# accessories.net
KiCad netlist of a schematic drawn in Altium Designer
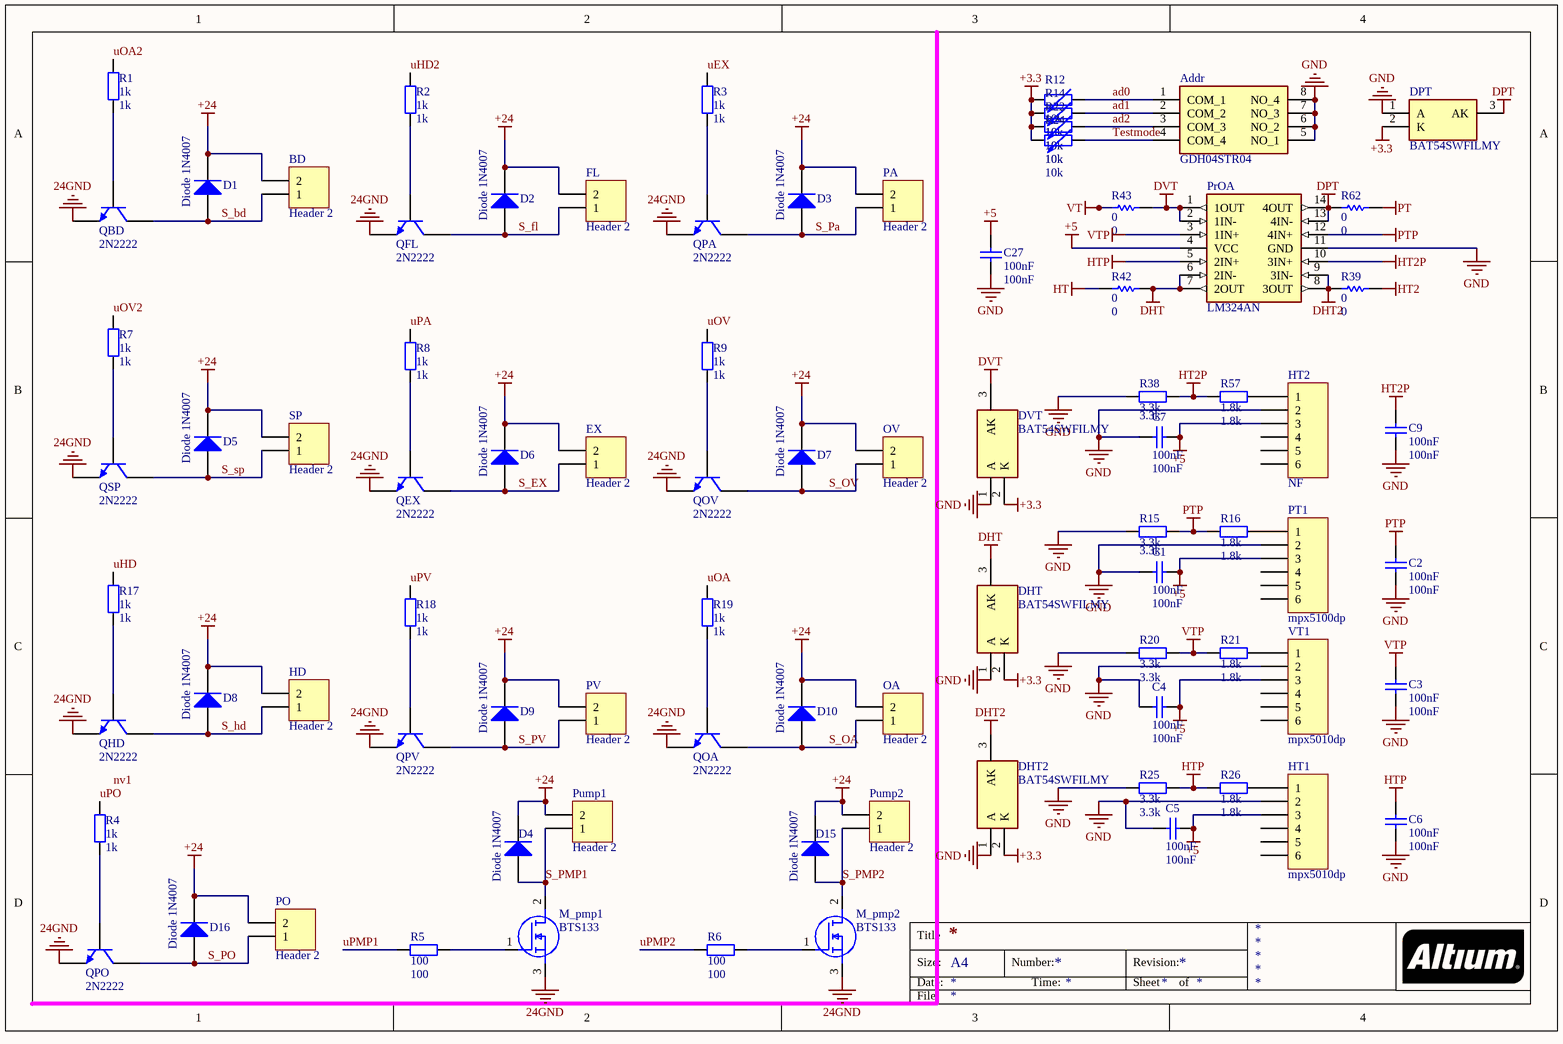
[diagram p0: accessories.SchDoc]

(export (version "E")
  (design (tool "Eeschema 10.0.6"))
  (components
    (comp (ref "Addr")
      (value "GDH04STR04")
      (footprint "SamacSys:GDH04STR04")
      (description "Switch")
      (fields (field (name "MOUSER PART NUMBER") "506-GDH04STR04"))
      (libsource (lib "*") (part "GDH04STR04"))
    )
    (comp (ref "BD")
      (value "Header 2")
      (footprint "PHOENIX2-Right")
      (description "Header, 2-Pin")
      (fields (field (name "PUBLISHER") "Altium Limited"))
      (libsource (lib "Miscellaneous Connectors") (part "Header 2"))
    )
    (comp (ref "C1")
      (value "100nF")
      (footprint "0805")
      (description "Capacitor")
      (fields (field (name "ALTIUM_VALUE") "100nF") (field (name "PUBLISHER") "Altium Limited"))
      (libsource (lib "Miscellaneous Devices") (part "Cap"))
    )
    (comp (ref "C2")
      (value "100nF")
      (footprint "0805")
      (description "Capacitor")
      (fields (field (name "ALTIUM_VALUE") "100nF") (field (name "PUBLISHER") "Altium Limited"))
      (libsource (lib "Miscellaneous Devices") (part "Cap"))
    )
    (comp (ref "C3")
      (value "100nF")
      (footprint "0805")
      (description "Capacitor")
      (fields (field (name "ALTIUM_VALUE") "100nF") (field (name "PUBLISHER") "Altium Limited"))
      (libsource (lib "Miscellaneous Devices") (part "Cap"))
    )
    (comp (ref "C4")
      (value "100nF")
      (footprint "0805")
      (description "Capacitor")
      (fields (field (name "ALTIUM_VALUE") "100nF") (field (name "PUBLISHER") "Altium Limited"))
      (libsource (lib "Miscellaneous Devices") (part "Cap"))
    )
    (comp (ref "C5")
      (value "100nF")
      (footprint "0805")
      (description "Capacitor")
      (fields (field (name "ALTIUM_VALUE") "100nF") (field (name "PUBLISHER") "Altium Limited"))
      (libsource (lib "Miscellaneous Devices") (part "Cap"))
    )
    (comp (ref "C6")
      (value "100nF")
      (footprint "0805")
      (description "Capacitor")
      (fields (field (name "ALTIUM_VALUE") "100nF") (field (name "PUBLISHER") "Altium Limited"))
      (libsource (lib "Miscellaneous Devices") (part "Cap"))
    )
    (comp (ref "C7")
      (value "100nF")
      (footprint "0805")
      (description "Capacitor")
      (fields (field (name "ALTIUM_VALUE") "100nF") (field (name "PUBLISHER") "Altium Limited"))
      (libsource (lib "Miscellaneous Devices") (part "Cap"))
    )
    (comp (ref "C9")
      (value "100nF")
      (footprint "0805")
      (description "Capacitor")
      (fields (field (name "ALTIUM_VALUE") "100nF") (field (name "PUBLISHER") "Altium Limited"))
      (libsource (lib "Miscellaneous Devices") (part "Cap"))
    )
    (comp (ref "C27")
      (value "100nF")
      (footprint "0805")
      (description "Capacitor")
      (fields
        (field (name "MANUFACTURER") "Generic Components")
        (field (name "ALTIUM_VALUE") "100nF")
        (field (name "PUBLISHER") "Altium Hobart Technology Centre")
      )
      (libsource (lib "Miscellaneous Devices") (part "Cap"))
    )
    (comp (ref "D1")
      (value "Diode 1N4007")
      (footprint "DO-41")
      (description "1 Amp General Purpose Rectifier")
      (fields (field (name "PUBLISHER") "Altium Limited"))
      (libsource (lib "Miscellaneous Devices") (part "Diode 1N4007"))
    )
    (comp (ref "D2")
      (value "Diode 1N4007")
      (footprint "DO-41")
      (description "1 Amp General Purpose Rectifier")
      (fields (field (name "PUBLISHER") "Altium Limited"))
      (libsource (lib "Miscellaneous Devices") (part "Diode 1N4007"))
    )
    (comp (ref "D3")
      (value "Diode 1N4007")
      (footprint "DO-41")
      (description "1 Amp General Purpose Rectifier")
      (fields (field (name "PUBLISHER") "Altium Limited"))
      (libsource (lib "Miscellaneous Devices") (part "Diode 1N4007"))
    )
    (comp (ref "D4")
      (value "Diode 1N4007")
      (footprint "DO-41")
      (description "1 Amp General Purpose Rectifier")
      (fields (field (name "PUBLISHER") "Altium Limited"))
      (libsource (lib "Miscellaneous Devices") (part "Diode 1N4007"))
    )
    (comp (ref "D5")
      (value "Diode 1N4007")
      (footprint "DO-41")
      (description "1 Amp General Purpose Rectifier")
      (fields (field (name "PUBLISHER") "Altium Limited"))
      (libsource (lib "Miscellaneous Devices") (part "Diode 1N4007"))
    )
    (comp (ref "D6")
      (value "Diode 1N4007")
      (footprint "DO-41")
      (description "1 Amp General Purpose Rectifier")
      (fields (field (name "PUBLISHER") "Altium Limited"))
      (libsource (lib "Miscellaneous Devices") (part "Diode 1N4007"))
    )
    (comp (ref "D7")
      (value "Diode 1N4007")
      (footprint "DO-41")
      (description "1 Amp General Purpose Rectifier")
      (fields (field (name "PUBLISHER") "Altium Limited"))
      (libsource (lib "Miscellaneous Devices") (part "Diode 1N4007"))
    )
    (comp (ref "D8")
      (value "Diode 1N4007")
      (footprint "DO-41")
      (description "1 Amp General Purpose Rectifier")
      (fields (field (name "PUBLISHER") "Altium Limited"))
      (libsource (lib "Miscellaneous Devices") (part "Diode 1N4007"))
    )
    (comp (ref "D9")
      (value "Diode 1N4007")
      (footprint "DO-41")
      (description "1 Amp General Purpose Rectifier")
      (fields (field (name "PUBLISHER") "Altium Limited"))
      (libsource (lib "Miscellaneous Devices") (part "Diode 1N4007"))
    )
    (comp (ref "D10")
      (value "Diode 1N4007")
      (footprint "DO-41")
      (description "1 Amp General Purpose Rectifier")
      (fields (field (name "PUBLISHER") "Altium Limited"))
      (libsource (lib "Miscellaneous Devices") (part "Diode 1N4007"))
    )
    (comp (ref "D15")
      (value "Diode 1N4007")
      (footprint "DO-41")
      (description "1 Amp General Purpose Rectifier")
      (fields (field (name "PUBLISHER") "Altium Limited"))
      (libsource (lib "Miscellaneous Devices") (part "Diode 1N4007"))
    )
    (comp (ref "D16")
      (value "Diode 1N4007")
      (footprint "DO-41")
      (description "1 Amp General Purpose Rectifier")
      (fields (field (name "PUBLISHER") "Altium Limited"))
      (libsource (lib "Miscellaneous Devices") (part "Diode 1N4007"))
    )
    (comp (ref "DHT")
      (value "BAT54SWFILMY")
      (footprint "psm712")
      (description "Schottky Diode")
      (fields (field (name "MOUSER PART NUMBER") "511-BAT54SWFILMY"))
      (libsource (lib "") (part "BAT54SWFILMY_1"))
    )
    (comp (ref "DHT2")
      (value "BAT54SWFILMY")
      (footprint "psm712")
      (description "Schottky Diode")
      (fields (field (name "MOUSER PART NUMBER") "511-BAT54SWFILMY"))
      (libsource (lib "") (part "BAT54SWFILMY_1"))
    )
    (comp (ref "DPT")
      (value "BAT54SWFILMY")
      (footprint "psm712")
      (description "Schottky Diode")
      (fields (field (name "MOUSER PART NUMBER") "511-BAT54SWFILMY"))
      (libsource (lib "*") (part "BAT54SWFILMY"))
    )
    (comp (ref "DVT")
      (value "BAT54SWFILMY")
      (footprint "psm712")
      (description "Schottky Diode")
      (fields (field (name "MOUSER PART NUMBER") "511-BAT54SWFILMY"))
      (libsource (lib "") (part "BAT54SWFILMY_1"))
    )
    (comp (ref "EX")
      (value "Header 2")
      (footprint "PHOENIX2-Right")
      (description "Header, 2-Pin")
      (fields (field (name "PUBLISHER") "Altium Limited"))
      (libsource (lib "Miscellaneous Connectors") (part "Header 2"))
    )
    (comp (ref "FL")
      (value "Header 2")
      (footprint "PHOENIX2-Right")
      (description "Header, 2-Pin")
      (fields (field (name "PUBLISHER") "Altium Limited"))
      (libsource (lib "Miscellaneous Connectors") (part "Header 2"))
    )
    (comp (ref "HD")
      (value "Header 2")
      (footprint "PHOENIX2-Right")
      (description "Header, 2-Pin")
      (fields (field (name "PUBLISHER") "Altium Limited"))
      (libsource (lib "Miscellaneous Connectors") (part "Header 2"))
    )
    (comp (ref "HT1")
      (value "mpx5010dp")
      (footprint "mpx-dp")
      (description "Header, 6-Pin")
      (fields (field (name "PUBLISHER") "Altium Limited"))
      (libsource (lib "Miscellaneous Connectors") (part "Header 6"))
    )
    (comp (ref "HT2")
      (value "NF")
      (footprint "mpx-dp")
      (description "Header, 6-Pin")
      (fields (field (name "PUBLISHER") "Altium Limited"))
      (libsource (lib "Miscellaneous Connectors") (part "Header 6"))
    )
    (comp (ref "M_pmp1")
      (value "BTS133")
      (footprint "SamacSys:IPB026N06NATMA1")
      (description "MOSFET (N-Channel)")
      (fields
        (field (name "MANUFACTURER_PART_NUMBER") "IPB026N06NATMA1")
        (field (name "MOUSER PART NUMBER") "726-IPB026N06NATMA1")
      )
      (libsource (lib "*") (part "IPB026N06NATMA1"))
    )
    (comp (ref "M_pmp2")
      (value "BTS133")
      (footprint "SamacSys:IPB026N06NATMA1")
      (description "MOSFET (N-Channel)")
      (fields
        (field (name "MANUFACTURER_PART_NUMBER") "IPB026N06NATMA1")
        (field (name "MOUSER PART NUMBER") "726-IPB026N06NATMA1")
      )
      (libsource (lib "*") (part "IPB026N06NATMA1"))
    )
    (comp (ref "OA")
      (value "Header 2")
      (footprint "PHOENIX2-Right")
      (description "Header, 2-Pin")
      (fields (field (name "PUBLISHER") "Altium Limited"))
      (libsource (lib "Miscellaneous Connectors") (part "Header 2"))
    )
    (comp (ref "OV")
      (value "Header 2")
      (footprint "PHOENIX2-Right")
      (description "Header, 2-Pin")
      (fields (field (name "PUBLISHER") "Altium Limited"))
      (libsource (lib "Miscellaneous Connectors") (part "Header 2"))
    )
    (comp (ref "PA")
      (value "Header 2")
      (footprint "PHOENIX2-Right")
      (description "Header, 2-Pin")
      (fields (field (name "PUBLISHER") "Altium Limited"))
      (libsource (lib "Miscellaneous Connectors") (part "Header 2"))
    )
    (comp (ref "PO")
      (value "Header 2")
      (footprint "PHOENIX2-right")
      (description "Header, 2-Pin")
      (fields (field (name "PUBLISHER") "Altium Limited"))
      (libsource (lib "Miscellaneous Connectors") (part "Header 2"))
    )
    (comp (ref "PrOA")
      (value "LM324AN")
      (footprint "DIP254P762X432-14")
      (description "Integrated Circuit")
      (fields (field (name "MOUSER PART NUMBER") "595-LM324AN") (field (name "RS PART NUMBER") "0527732"))
      (libsource (lib "*") (part "LM324AN"))
    )
    (comp (ref "PT1")
      (value "mpx5100dp")
      (footprint "mpx-dp")
      (description "Header, 6-Pin")
      (fields (field (name "PUBLISHER") "Altium Limited"))
      (libsource (lib "Miscellaneous Connectors") (part "Header 6"))
    )
    (comp (ref "Pump1")
      (value "Header 2")
      (footprint "PHOENIX2-Right")
      (description "Header, 2-Pin")
      (fields (field (name "PUBLISHER") "Altium Limited"))
      (libsource (lib "Miscellaneous Connectors") (part "Header 2"))
    )
    (comp (ref "Pump2")
      (value "Header 2")
      (footprint "PHOENIX2-Right")
      (description "Header, 2-Pin")
      (fields (field (name "PUBLISHER") "Altium Limited"))
      (libsource (lib "Miscellaneous Connectors") (part "Header 2"))
    )
    (comp (ref "PV")
      (value "Header 2")
      (footprint "PHOENIX2-Right")
      (description "Header, 2-Pin")
      (fields (field (name "PUBLISHER") "Altium Limited"))
      (libsource (lib "Miscellaneous Connectors") (part "Header 2"))
    )
    (comp (ref "QBD")
      (value "2N2222")
      (footprint "2n2222")
      (description "NPN General Purpose Amplifier")
      (fields (field (name "PUBLISHER") "Altium Limited"))
      (libsource (lib "Miscellaneous Devices") (part "2N3904"))
    )
    (comp (ref "QEX")
      (value "2N2222")
      (footprint "2n2222")
      (description "NPN General Purpose Amplifier")
      (fields (field (name "PUBLISHER") "Altium Limited"))
      (libsource (lib "Miscellaneous Devices") (part "2N3904"))
    )
    (comp (ref "QFL")
      (value "2N2222")
      (footprint "2n2222")
      (description "NPN General Purpose Amplifier")
      (fields (field (name "PUBLISHER") "Altium Limited"))
      (libsource (lib "Miscellaneous Devices") (part "2N3904"))
    )
    (comp (ref "QHD")
      (value "2N2222")
      (footprint "2n2222")
      (description "NPN General Purpose Amplifier")
      (fields (field (name "PUBLISHER") "Altium Limited"))
      (libsource (lib "Miscellaneous Devices") (part "2N3904"))
    )
    (comp (ref "QOA")
      (value "2N2222")
      (footprint "2n2222")
      (description "NPN General Purpose Amplifier")
      (fields (field (name "PUBLISHER") "Altium Limited"))
      (libsource (lib "Miscellaneous Devices") (part "2N3904"))
    )
    (comp (ref "QOV")
      (value "2N2222")
      (footprint "2n2222")
      (description "NPN General Purpose Amplifier")
      (fields (field (name "PUBLISHER") "Altium Limited"))
      (libsource (lib "Miscellaneous Devices") (part "2N3904"))
    )
    (comp (ref "QPA")
      (value "2N2222")
      (footprint "2n2222")
      (description "NPN General Purpose Amplifier")
      (fields (field (name "PUBLISHER") "Altium Limited"))
      (libsource (lib "Miscellaneous Devices") (part "2N3904"))
    )
    (comp (ref "QPO")
      (value "2N2222")
      (footprint "2n2222")
      (description "NPN General Purpose Amplifier")
      (fields (field (name "PUBLISHER") "Altium Limited"))
      (libsource (lib "Miscellaneous Devices") (part "2N3904"))
    )
    (comp (ref "QPV")
      (value "2N2222")
      (footprint "2n2222")
      (description "NPN General Purpose Amplifier")
      (fields (field (name "PUBLISHER") "Altium Limited"))
      (libsource (lib "Miscellaneous Devices") (part "2N3904"))
    )
    (comp (ref "QSP")
      (value "2N2222")
      (footprint "2n2222")
      (description "NPN General Purpose Amplifier")
      (fields (field (name "PUBLISHER") "Altium Limited"))
      (libsource (lib "Miscellaneous Devices") (part "2N3904"))
    )
    (comp (ref "R1")
      (value "1k")
      (footprint "0805")
      (description "Resistor")
      (fields (field (name "ALTIUM_VALUE") "1k") (field (name "PUBLISHER") "Altium Limited"))
      (libsource (lib "Miscellaneous Devices") (part "Res2"))
    )
    (comp (ref "R2")
      (value "1k")
      (footprint "0805")
      (description "Resistor")
      (fields (field (name "ALTIUM_VALUE") "1k") (field (name "PUBLISHER") "Altium Limited"))
      (libsource (lib "Miscellaneous Devices") (part "Res2"))
    )
    (comp (ref "R3")
      (value "1k")
      (footprint "0805")
      (description "Resistor")
      (fields (field (name "ALTIUM_VALUE") "1k") (field (name "PUBLISHER") "Altium Limited"))
      (libsource (lib "Miscellaneous Devices") (part "Res2"))
    )
    (comp (ref "R4")
      (value "1k")
      (footprint "0805")
      (description "Resistor")
      (fields (field (name "ALTIUM_VALUE") "1k") (field (name "PUBLISHER") "Altium Limited"))
      (libsource (lib "Miscellaneous Devices") (part "Res2"))
    )
    (comp (ref "R5")
      (value "100")
      (footprint "0805")
      (description "Resistor")
      (fields (field (name "ALTIUM_VALUE") "100") (field (name "PUBLISHER") "Altium Limited"))
      (libsource (lib "") (part "Res2_1"))
    )
    (comp (ref "R6")
      (value "100")
      (footprint "0805")
      (description "Resistor")
      (fields (field (name "ALTIUM_VALUE") "100") (field (name "PUBLISHER") "Altium Limited"))
      (libsource (lib "") (part "Res2_1"))
    )
    (comp (ref "R7")
      (value "1k")
      (footprint "0805")
      (description "Resistor")
      (fields (field (name "ALTIUM_VALUE") "1k") (field (name "PUBLISHER") "Altium Limited"))
      (libsource (lib "Miscellaneous Devices") (part "Res2"))
    )
    (comp (ref "R8")
      (value "1k")
      (footprint "0805")
      (description "Resistor")
      (fields (field (name "ALTIUM_VALUE") "1k") (field (name "PUBLISHER") "Altium Limited"))
      (libsource (lib "Miscellaneous Devices") (part "Res2"))
    )
    (comp (ref "R9")
      (value "1k")
      (footprint "0805")
      (description "Resistor")
      (fields (field (name "ALTIUM_VALUE") "1k") (field (name "PUBLISHER") "Altium Limited"))
      (libsource (lib "Miscellaneous Devices") (part "Res2"))
    )
    (comp (ref "R12")
      (value "10k")
      (footprint "0805")
      (description "Variable Resistor")
      (fields (field (name "ALTIUM_VALUE") "10k") (field (name "PUBLISHER") "Altium Limited"))
      (libsource (lib "Miscellaneous Devices") (part "Res Adj2"))
    )
    (comp (ref "R14")
      (value "10k")
      (footprint "0805")
      (description "Variable Resistor")
      (fields (field (name "ALTIUM_VALUE") "10k") (field (name "PUBLISHER") "Altium Limited"))
      (libsource (lib "Miscellaneous Devices") (part "Res Adj2"))
    )
    (comp (ref "R15")
      (value "3.3k")
      (footprint "0805")
      (description "Resistor")
      (fields (field (name "ALTIUM_VALUE") "3.3k") (field (name "PUBLISHER") "Altium Limited"))
      (libsource (lib "") (part "Res2_1"))
    )
    (comp (ref "R16")
      (value "1.8k")
      (footprint "0805")
      (description "Resistor")
      (fields (field (name "ALTIUM_VALUE") "1.8k") (field (name "PUBLISHER") "Altium Limited"))
      (libsource (lib "") (part "Res2_1"))
    )
    (comp (ref "R17")
      (value "1k")
      (footprint "0805")
      (description "Resistor")
      (fields (field (name "ALTIUM_VALUE") "1k") (field (name "PUBLISHER") "Altium Limited"))
      (libsource (lib "Miscellaneous Devices") (part "Res2"))
    )
    (comp (ref "R18")
      (value "1k")
      (footprint "0805")
      (description "Resistor")
      (fields (field (name "ALTIUM_VALUE") "1k") (field (name "PUBLISHER") "Altium Limited"))
      (libsource (lib "Miscellaneous Devices") (part "Res2"))
    )
    (comp (ref "R19")
      (value "1k")
      (footprint "0805")
      (description "Resistor")
      (fields (field (name "ALTIUM_VALUE") "1k") (field (name "PUBLISHER") "Altium Limited"))
      (libsource (lib "Miscellaneous Devices") (part "Res2"))
    )
    (comp (ref "R20")
      (value "3.3k")
      (footprint "0805")
      (description "Resistor")
      (fields (field (name "ALTIUM_VALUE") "3.3k") (field (name "PUBLISHER") "Altium Limited"))
      (libsource (lib "") (part "Res2_1"))
    )
    (comp (ref "R21")
      (value "1.8k")
      (footprint "0805")
      (description "Resistor")
      (fields (field (name "ALTIUM_VALUE") "1.8k") (field (name "PUBLISHER") "Altium Limited"))
      (libsource (lib "") (part "Res2_1"))
    )
    (comp (ref "R22")
      (value "10k")
      (footprint "0805")
      (description "Variable Resistor")
      (fields (field (name "ALTIUM_VALUE") "10k") (field (name "PUBLISHER") "Altium Limited"))
      (libsource (lib "Miscellaneous Devices") (part "Res Adj2"))
    )
    (comp (ref "R24")
      (value "10k")
      (footprint "0805")
      (description "Variable Resistor")
      (fields (field (name "ALTIUM_VALUE") "10k") (field (name "PUBLISHER") "Altium Limited"))
      (libsource (lib "Miscellaneous Devices") (part "Res Adj2"))
    )
    (comp (ref "R25")
      (value "3.3k")
      (footprint "0805")
      (description "Resistor")
      (fields (field (name "ALTIUM_VALUE") "3.3k") (field (name "PUBLISHER") "Altium Limited"))
      (libsource (lib "") (part "Res2_1"))
    )
    (comp (ref "R26")
      (value "1.8k")
      (footprint "0805")
      (description "Resistor")
      (fields (field (name "ALTIUM_VALUE") "1.8k") (field (name "PUBLISHER") "Altium Limited"))
      (libsource (lib "") (part "Res2_1"))
    )
    (comp (ref "R38")
      (value "3.3k")
      (footprint "0805")
      (description "Resistor")
      (fields (field (name "ALTIUM_VALUE") "3.3k") (field (name "PUBLISHER") "Altium Limited"))
      (libsource (lib "") (part "Res2_1"))
    )
    (comp (ref "R39")
      (value "0")
      (footprint "0805")
      (description "Resistor")
      (fields (field (name "ALTIUM_VALUE") "0") (field (name "PUBLISHER") "Altium Limited"))
      (libsource (lib "Miscellaneous Devices") (part "Res1"))
    )
    (comp (ref "R42")
      (value "0")
      (footprint "0805")
      (description "Resistor")
      (fields (field (name "ALTIUM_VALUE") "0") (field (name "PUBLISHER") "Altium Limited"))
      (libsource (lib "Miscellaneous Devices") (part "Res1"))
    )
    (comp (ref "R43")
      (value "0")
      (footprint "0805")
      (description "Resistor")
      (fields (field (name "ALTIUM_VALUE") "0") (field (name "PUBLISHER") "Altium Limited"))
      (libsource (lib "Miscellaneous Devices") (part "Res1"))
    )
    (comp (ref "R57")
      (value "1.8k")
      (footprint "0805")
      (description "Resistor")
      (fields (field (name "ALTIUM_VALUE") "1.8k") (field (name "PUBLISHER") "Altium Limited"))
      (libsource (lib "") (part "Res2_1"))
    )
    (comp (ref "R62")
      (value "0")
      (footprint "0805")
      (description "Resistor")
      (fields (field (name "ALTIUM_VALUE") "0") (field (name "PUBLISHER") "Altium Limited"))
      (libsource (lib "Miscellaneous Devices") (part "Res1"))
    )
    (comp (ref "SP")
      (value "Header 2")
      (footprint "PHOENIX2-Right")
      (description "Header, 2-Pin")
      (fields (field (name "PUBLISHER") "Altium Limited"))
      (libsource (lib "Miscellaneous Connectors") (part "Header 2"))
    )
    (comp (ref "VT1")
      (value "mpx5010dp")
      (footprint "mpx-dp")
      (description "Header, 6-Pin")
      (fields (field (name "PUBLISHER") "Altium Limited"))
      (libsource (lib "Miscellaneous Connectors") (part "Header 6"))
    )
  )
  (nets
    (net (code "1") (name "+3.3") (class "Default")
      (node (ref "DHT") (pin "2") (pinfunction "K_2") (pintype "passive"))
      (node (ref "DHT2") (pin "2") (pinfunction "K_2") (pintype "passive"))
      (node (ref "DPT") (pin "2") (pinfunction "K_2") (pintype "passive"))
      (node (ref "DVT") (pin "2") (pinfunction "K_2") (pintype "passive"))
      (node (ref "R12") (pin "2") (pinfunction "2_2") (pintype "passive"))
      (node (ref "R14") (pin "2") (pinfunction "2_2") (pintype "passive"))
      (node (ref "R22") (pin "2") (pinfunction "2_2") (pintype "passive"))
      (node (ref "R24") (pin "2") (pinfunction "2_2") (pintype "passive"))
    )
    (net (code "2") (name "+5") (class "Default")
      (node (ref "C1") (pin "1") (pinfunction "1_1") (pintype "passive"))
      (node (ref "C27") (pin "2") (pinfunction "2_2") (pintype "passive"))
      (node (ref "C4") (pin "1") (pinfunction "1_1") (pintype "passive"))
      (node (ref "C5") (pin "1") (pinfunction "1_1") (pintype "passive"))
      (node (ref "C7") (pin "1") (pinfunction "1_1") (pintype "passive"))
      (node (ref "HT1") (pin "3") (pinfunction "3_3") (pintype "passive"))
      (node (ref "HT2") (pin "3") (pinfunction "3_3") (pintype "passive"))
      (node (ref "PT1") (pin "3") (pinfunction "3_3") (pintype "passive"))
      (node (ref "PrOA") (pin "4") (pinfunction "VCC_4") (pintype "power_in"))
      (node (ref "VT1") (pin "3") (pinfunction "3_3") (pintype "passive"))
    )
    (net (code "3") (name "+24") (class "Default")
      (node (ref "BD") (pin "2") (pinfunction "2_2") (pintype "passive"))
      (node (ref "D1") (pin "2") (pinfunction "K_2") (pintype "passive"))
      (node (ref "D10") (pin "2") (pinfunction "K_2") (pintype "passive"))
      (node (ref "D15") (pin "2") (pinfunction "K_2") (pintype "passive"))
      (node (ref "D16") (pin "2") (pinfunction "K_2") (pintype "passive"))
      (node (ref "D2") (pin "2") (pinfunction "K_2") (pintype "passive"))
      (node (ref "D3") (pin "2") (pinfunction "K_2") (pintype "passive"))
      (node (ref "D4") (pin "2") (pinfunction "K_2") (pintype "passive"))
      (node (ref "D5") (pin "2") (pinfunction "K_2") (pintype "passive"))
      (node (ref "D6") (pin "2") (pinfunction "K_2") (pintype "passive"))
      (node (ref "D7") (pin "2") (pinfunction "K_2") (pintype "passive"))
      (node (ref "D8") (pin "2") (pinfunction "K_2") (pintype "passive"))
      (node (ref "D9") (pin "2") (pinfunction "K_2") (pintype "passive"))
      (node (ref "EX") (pin "2") (pinfunction "2_2") (pintype "passive"))
      (node (ref "FL") (pin "2") (pinfunction "2_2") (pintype "passive"))
      (node (ref "HD") (pin "2") (pinfunction "2_2") (pintype "passive"))
      (node (ref "OA") (pin "2") (pinfunction "2_2") (pintype "passive"))
      (node (ref "OV") (pin "2") (pinfunction "2_2") (pintype "passive"))
      (node (ref "PA") (pin "2") (pinfunction "2_2") (pintype "passive"))
      (node (ref "PO") (pin "2") (pinfunction "2_2") (pintype "passive"))
      (node (ref "PV") (pin "2") (pinfunction "2_2") (pintype "passive"))
      (node (ref "Pump1") (pin "2") (pinfunction "2_2") (pintype "passive"))
      (node (ref "Pump2") (pin "2") (pinfunction "2_2") (pintype "passive"))
      (node (ref "SP") (pin "2") (pinfunction "2_2") (pintype "passive"))
    )
    (net (code "4") (name "/S_EX") (class "Default")
      (node (ref "D6") (pin "1") (pinfunction "A_1") (pintype "passive"))
      (node (ref "EX") (pin "1") (pinfunction "1_1") (pintype "passive"))
      (node (ref "QEX") (pin "3") (pinfunction "C_3") (pintype "passive"))
    )
    (net (code "5") (name "/S_OA") (class "Default")
      (node (ref "D10") (pin "1") (pinfunction "A_1") (pintype "passive"))
      (node (ref "OA") (pin "1") (pinfunction "1_1") (pintype "passive"))
      (node (ref "QOA") (pin "3") (pinfunction "C_3") (pintype "passive"))
    )
    (net (code "6") (name "/S_OV") (class "Default")
      (node (ref "D7") (pin "1") (pinfunction "A_1") (pintype "passive"))
      (node (ref "OV") (pin "1") (pinfunction "1_1") (pintype "passive"))
      (node (ref "QOV") (pin "3") (pinfunction "C_3") (pintype "passive"))
    )
    (net (code "7") (name "/S_PMP1") (class "Default")
      (node (ref "D4") (pin "1") (pinfunction "A_1") (pintype "passive"))
      (node (ref "M_pmp1") (pin "2") (pinfunction "D_2") (pintype "passive"))
      (node (ref "Pump1") (pin "1") (pinfunction "1_1") (pintype "passive"))
    )
    (net (code "8") (name "/S_PMP2") (class "Default")
      (node (ref "D15") (pin "1") (pinfunction "A_1") (pintype "passive"))
      (node (ref "M_pmp2") (pin "2") (pinfunction "D_2") (pintype "passive"))
      (node (ref "Pump2") (pin "1") (pinfunction "1_1") (pintype "passive"))
    )
    (net (code "9") (name "/S_PO") (class "Default")
      (node (ref "D16") (pin "1") (pinfunction "A_1") (pintype "passive"))
      (node (ref "PO") (pin "1") (pinfunction "1_1") (pintype "passive"))
      (node (ref "QPO") (pin "3") (pinfunction "C_3") (pintype "passive"))
    )
    (net (code "10") (name "/S_PV") (class "Default")
      (node (ref "D9") (pin "1") (pinfunction "A_1") (pintype "passive"))
      (node (ref "PV") (pin "1") (pinfunction "1_1") (pintype "passive"))
      (node (ref "QPV") (pin "3") (pinfunction "C_3") (pintype "passive"))
    )
    (net (code "11") (name "/S_Pa") (class "Default")
      (node (ref "D3") (pin "1") (pinfunction "A_1") (pintype "passive"))
      (node (ref "PA") (pin "1") (pinfunction "1_1") (pintype "passive"))
      (node (ref "QPA") (pin "3") (pinfunction "C_3") (pintype "passive"))
    )
    (net (code "12") (name "/S_bd") (class "Default")
      (node (ref "BD") (pin "1") (pinfunction "1_1") (pintype "passive"))
      (node (ref "D1") (pin "1") (pinfunction "A_1") (pintype "passive"))
      (node (ref "QBD") (pin "3") (pinfunction "C_3") (pintype "passive"))
    )
    (net (code "13") (name "/S_fl") (class "Default")
      (node (ref "D2") (pin "1") (pinfunction "A_1") (pintype "passive"))
      (node (ref "FL") (pin "1") (pinfunction "1_1") (pintype "passive"))
      (node (ref "QFL") (pin "3") (pinfunction "C_3") (pintype "passive"))
    )
    (net (code "14") (name "/S_hd") (class "Default")
      (node (ref "D8") (pin "1") (pinfunction "A_1") (pintype "passive"))
      (node (ref "HD") (pin "1") (pinfunction "1_1") (pintype "passive"))
      (node (ref "QHD") (pin "3") (pinfunction "C_3") (pintype "passive"))
    )
    (net (code "15") (name "/S_sp") (class "Default")
      (node (ref "D5") (pin "1") (pinfunction "A_1") (pintype "passive"))
      (node (ref "QSP") (pin "3") (pinfunction "C_3") (pintype "passive"))
      (node (ref "SP") (pin "1") (pinfunction "1_1") (pintype "passive"))
    )
    (net (code "16") (name "/Testmode") (class "Default")
      (node (ref "Addr") (pin "4") (pinfunction "COM_4_4") (pintype "passive"))
      (node (ref "R24") (pin "1") (pinfunction "1_1") (pintype "passive"))
    )
    (net (code "17") (name "/ad0") (class "Default")
      (node (ref "Addr") (pin "1") (pinfunction "COM_1_1") (pintype "passive"))
      (node (ref "R12") (pin "1") (pinfunction "1_1") (pintype "passive"))
    )
    (net (code "18") (name "/ad1") (class "Default")
      (node (ref "Addr") (pin "2") (pinfunction "COM_2_2") (pintype "passive"))
      (node (ref "R14") (pin "1") (pinfunction "1_1") (pintype "passive"))
    )
    (net (code "19") (name "/ad2") (class "Default")
      (node (ref "Addr") (pin "3") (pinfunction "COM_3_3") (pintype "passive"))
      (node (ref "R22") (pin "1") (pinfunction "1_1") (pintype "passive"))
    )
    (net (code "21") (name "/uEX") (class "Default")
      (node (ref "R3") (pin "1") (pinfunction "1_1") (pintype "passive"))
    )
    (net (code "22") (name "/uHD") (class "Default")
      (node (ref "R17") (pin "1") (pinfunction "1_1") (pintype "passive"))
    )
    (net (code "23") (name "/uHD2") (class "Default")
      (node (ref "R2") (pin "1") (pinfunction "1_1") (pintype "passive"))
    )
    (net (code "24") (name "/uOA") (class "Default")
      (node (ref "R19") (pin "1") (pinfunction "1_1") (pintype "passive"))
    )
    (net (code "25") (name "/uOA2") (class "Default")
      (node (ref "R1") (pin "1") (pinfunction "1_1") (pintype "passive"))
    )
    (net (code "26") (name "/uOV") (class "Default")
      (node (ref "R9") (pin "1") (pinfunction "1_1") (pintype "passive"))
    )
    (net (code "27") (name "/uOV2") (class "Default")
      (node (ref "R7") (pin "1") (pinfunction "1_1") (pintype "passive"))
    )
    (net (code "28") (name "/uPA") (class "Default")
      (node (ref "R8") (pin "1") (pinfunction "1_1") (pintype "passive"))
    )
    (net (code "29") (name "/uPMP1") (class "Default")
      (node (ref "R5") (pin "1") (pinfunction "1_1") (pintype "passive"))
    )
    (net (code "30") (name "/uPMP2") (class "Default")
      (node (ref "R6") (pin "1") (pinfunction "1_1") (pintype "passive"))
    )
    (net (code "31") (name "/uPO") (class "Default")
      (node (ref "R4") (pin "1") (pinfunction "1_1") (pintype "passive"))
    )
    (net (code "32") (name "/uPV") (class "Default")
      (node (ref "R18") (pin "1") (pinfunction "1_1") (pintype "passive"))
    )
    (net (code "33") (name "24GND") (class "Default")
      (node (ref "M_pmp1") (pin "3") (pinfunction "S_3") (pintype "passive"))
      (node (ref "M_pmp2") (pin "3") (pinfunction "S_3") (pintype "passive"))
      (node (ref "QBD") (pin "1") (pinfunction "E_1") (pintype "passive"))
      (node (ref "QEX") (pin "1") (pinfunction "E_1") (pintype "passive"))
      (node (ref "QFL") (pin "1") (pinfunction "E_1") (pintype "passive"))
      (node (ref "QHD") (pin "1") (pinfunction "E_1") (pintype "passive"))
      (node (ref "QOA") (pin "1") (pinfunction "E_1") (pintype "passive"))
      (node (ref "QOV") (pin "1") (pinfunction "E_1") (pintype "passive"))
      (node (ref "QPA") (pin "1") (pinfunction "E_1") (pintype "passive"))
      (node (ref "QPO") (pin "1") (pinfunction "E_1") (pintype "passive"))
      (node (ref "QPV") (pin "1") (pinfunction "E_1") (pintype "passive"))
      (node (ref "QSP") (pin "1") (pinfunction "E_1") (pintype "passive"))
    )
    (net (code "34") (name "DHT") (class "Default")
      (node (ref "DHT") (pin "3") (pinfunction "AK_3") (pintype "passive"))
      (node (ref "PrOA") (pin "6") (pinfunction "2IN-_6") (pintype "input"))
      (node (ref "PrOA") (pin "7") (pinfunction "2OUT_7") (pintype "output"))
      (node (ref "R42") (pin "1") (pinfunction "1_1") (pintype "passive"))
    )
    (net (code "35") (name "DHT2") (class "Default")
      (node (ref "DHT2") (pin "3") (pinfunction "AK_3") (pintype "passive"))
      (node (ref "PrOA") (pin "8") (pinfunction "3OUT_8") (pintype "output"))
      (node (ref "PrOA") (pin "9") (pinfunction "3IN-_9") (pintype "input"))
      (node (ref "R39") (pin "1") (pinfunction "1_1") (pintype "passive"))
    )
    (net (code "36") (name "DPT") (class "Default")
      (node (ref "DPT") (pin "3") (pinfunction "AK_3") (pintype "passive"))
      (node (ref "PrOA") (pin "13") (pinfunction "4IN-_13") (pintype "input"))
      (node (ref "PrOA") (pin "14") (pinfunction "4OUT_14") (pintype "output"))
      (node (ref "R62") (pin "1") (pinfunction "1_1") (pintype "passive"))
    )
    (net (code "37") (name "DVT") (class "Default")
      (node (ref "DVT") (pin "3") (pinfunction "AK_3") (pintype "passive"))
      (node (ref "PrOA") (pin "1") (pinfunction "1OUT_1") (pintype "output"))
      (node (ref "PrOA") (pin "2") (pinfunction "1IN-_2") (pintype "input"))
      (node (ref "R43") (pin "2") (pinfunction "2_2") (pintype "passive"))
    )
    (net (code "38") (name "GND") (class "Default")
      (node (ref "Addr") (pin "5") (pinfunction "NO_1_5") (pintype "passive"))
      (node (ref "Addr") (pin "6") (pinfunction "NO_2_6") (pintype "passive"))
      (node (ref "Addr") (pin "7") (pinfunction "NO_3_7") (pintype "passive"))
      (node (ref "Addr") (pin "8") (pinfunction "NO_4_8") (pintype "passive"))
      (node (ref "C1") (pin "2") (pinfunction "2_2") (pintype "passive"))
      (node (ref "C2") (pin "2") (pinfunction "2_2") (pintype "passive"))
      (node (ref "C27") (pin "1") (pinfunction "1_1") (pintype "passive"))
      (node (ref "C3") (pin "2") (pinfunction "2_2") (pintype "passive"))
      (node (ref "C4") (pin "2") (pinfunction "2_2") (pintype "passive"))
      (node (ref "C5") (pin "2") (pinfunction "2_2") (pintype "passive"))
      (node (ref "C6") (pin "2") (pinfunction "2_2") (pintype "passive"))
      (node (ref "C7") (pin "2") (pinfunction "2_2") (pintype "passive"))
      (node (ref "C9") (pin "2") (pinfunction "2_2") (pintype "passive"))
      (node (ref "DHT") (pin "1") (pinfunction "A_1") (pintype "passive"))
      (node (ref "DHT2") (pin "1") (pinfunction "A_1") (pintype "passive"))
      (node (ref "DPT") (pin "1") (pinfunction "A_1") (pintype "passive"))
      (node (ref "DVT") (pin "1") (pinfunction "A_1") (pintype "passive"))
      (node (ref "HT1") (pin "2") (pinfunction "2_2") (pintype "passive"))
      (node (ref "HT2") (pin "2") (pinfunction "2_2") (pintype "passive"))
      (node (ref "PT1") (pin "2") (pinfunction "2_2") (pintype "passive"))
      (node (ref "PrOA") (pin "11") (pinfunction "GND_11") (pintype "power_in"))
      (node (ref "R15") (pin "1") (pinfunction "1_1") (pintype "passive"))
      (node (ref "R20") (pin "1") (pinfunction "1_1") (pintype "passive"))
      (node (ref "R25") (pin "1") (pinfunction "1_1") (pintype "passive"))
      (node (ref "R38") (pin "1") (pinfunction "1_1") (pintype "passive"))
      (node (ref "VT1") (pin "2") (pinfunction "2_2") (pintype "passive"))
    )
    (net (code "39") (name "HT") (class "Default")
      (node (ref "R42") (pin "2") (pinfunction "2_2") (pintype "passive"))
    )
    (net (code "40") (name "HT2") (class "Default")
      (node (ref "R39") (pin "2") (pinfunction "2_2") (pintype "passive"))
    )
    (net (code "41") (name "HT2P") (class "Default")
      (node (ref "C9") (pin "1") (pinfunction "1_1") (pintype "passive"))
      (node (ref "PrOA") (pin "10") (pinfunction "3IN+_10") (pintype "input"))
      (node (ref "R38") (pin "2") (pinfunction "2_2") (pintype "passive"))
      (node (ref "R57") (pin "1") (pinfunction "1_1") (pintype "passive"))
    )
    (net (code "42") (name "HTP") (class "Default")
      (node (ref "C6") (pin "1") (pinfunction "1_1") (pintype "passive"))
      (node (ref "PrOA") (pin "5") (pinfunction "2IN+_5") (pintype "input"))
      (node (ref "R25") (pin "2") (pinfunction "2_2") (pintype "passive"))
      (node (ref "R26") (pin "1") (pinfunction "1_1") (pintype "passive"))
    )
    (net (code "43") (name "Net-(HT1-Pad1)") (class "Default")
      (node (ref "HT1") (pin "1") (pinfunction "1_1") (pintype "passive"))
      (node (ref "R26") (pin "2") (pinfunction "2_2") (pintype "passive"))
    )
    (net (code "44") (name "Net-(HT2-Pad1)") (class "Default")
      (node (ref "HT2") (pin "1") (pinfunction "1_1") (pintype "passive"))
      (node (ref "R57") (pin "2") (pinfunction "2_2") (pintype "passive"))
    )
    (net (code "45") (name "Net-(M_pmp1-G)") (class "Default")
      (node (ref "M_pmp1") (pin "1") (pinfunction "G_1") (pintype "passive"))
      (node (ref "R5") (pin "2") (pinfunction "2_2") (pintype "passive"))
    )
    (net (code "46") (name "Net-(M_pmp2-G)") (class "Default")
      (node (ref "M_pmp2") (pin "1") (pinfunction "G_1") (pintype "passive"))
      (node (ref "R6") (pin "2") (pinfunction "2_2") (pintype "passive"))
    )
    (net (code "47") (name "Net-(PT1-Pad1)") (class "Default")
      (node (ref "PT1") (pin "1") (pinfunction "1_1") (pintype "passive"))
      (node (ref "R16") (pin "2") (pinfunction "2_2") (pintype "passive"))
    )
    (net (code "48") (name "Net-(QBD-B)") (class "Default")
      (node (ref "QBD") (pin "2") (pinfunction "B_2") (pintype "passive"))
      (node (ref "R1") (pin "2") (pinfunction "2_2") (pintype "passive"))
    )
    (net (code "49") (name "Net-(QEX-B)") (class "Default")
      (node (ref "QEX") (pin "2") (pinfunction "B_2") (pintype "passive"))
      (node (ref "R8") (pin "2") (pinfunction "2_2") (pintype "passive"))
    )
    (net (code "50") (name "Net-(QFL-B)") (class "Default")
      (node (ref "QFL") (pin "2") (pinfunction "B_2") (pintype "passive"))
      (node (ref "R2") (pin "2") (pinfunction "2_2") (pintype "passive"))
    )
    (net (code "51") (name "Net-(QHD-B)") (class "Default")
      (node (ref "QHD") (pin "2") (pinfunction "B_2") (pintype "passive"))
      (node (ref "R17") (pin "2") (pinfunction "2_2") (pintype "passive"))
    )
    (net (code "52") (name "Net-(QOA-B)") (class "Default")
      (node (ref "QOA") (pin "2") (pinfunction "B_2") (pintype "passive"))
      (node (ref "R19") (pin "2") (pinfunction "2_2") (pintype "passive"))
    )
    (net (code "53") (name "Net-(QOV-B)") (class "Default")
      (node (ref "QOV") (pin "2") (pinfunction "B_2") (pintype "passive"))
      (node (ref "R9") (pin "2") (pinfunction "2_2") (pintype "passive"))
    )
    (net (code "54") (name "Net-(QPA-B)") (class "Default")
      (node (ref "QPA") (pin "2") (pinfunction "B_2") (pintype "passive"))
      (node (ref "R3") (pin "2") (pinfunction "2_2") (pintype "passive"))
    )
    (net (code "55") (name "Net-(QPO-B)") (class "Default")
      (node (ref "QPO") (pin "2") (pinfunction "B_2") (pintype "passive"))
      (node (ref "R4") (pin "2") (pinfunction "2_2") (pintype "passive"))
    )
    (net (code "56") (name "Net-(QPV-B)") (class "Default")
      (node (ref "QPV") (pin "2") (pinfunction "B_2") (pintype "passive"))
      (node (ref "R18") (pin "2") (pinfunction "2_2") (pintype "passive"))
    )
    (net (code "57") (name "Net-(QSP-B)") (class "Default")
      (node (ref "QSP") (pin "2") (pinfunction "B_2") (pintype "passive"))
      (node (ref "R7") (pin "2") (pinfunction "2_2") (pintype "passive"))
    )
    (net (code "58") (name "Net-(R21-Pad2)") (class "Default")
      (node (ref "R21") (pin "2") (pinfunction "2_2") (pintype "passive"))
      (node (ref "VT1") (pin "1") (pinfunction "1_1") (pintype "passive"))
    )
    (net (code "59") (name "PT") (class "Default")
      (node (ref "R62") (pin "2") (pinfunction "2_2") (pintype "passive"))
    )
    (net (code "60") (name "PTP") (class "Default")
      (node (ref "C2") (pin "1") (pinfunction "1_1") (pintype "passive"))
      (node (ref "PrOA") (pin "12") (pinfunction "4IN+_12") (pintype "input"))
      (node (ref "R15") (pin "2") (pinfunction "2_2") (pintype "passive"))
      (node (ref "R16") (pin "1") (pinfunction "1_1") (pintype "passive"))
    )
    (net (code "61") (name "VT") (class "Default")
      (node (ref "R43") (pin "1") (pinfunction "1_1") (pintype "passive"))
    )
    (net (code "62") (name "VTP") (class "Default")
      (node (ref "C3") (pin "1") (pinfunction "1_1") (pintype "passive"))
      (node (ref "PrOA") (pin "3") (pinfunction "1IN+_3") (pintype "input"))
      (node (ref "R20") (pin "2") (pinfunction "2_2") (pintype "passive"))
      (node (ref "R21") (pin "1") (pinfunction "1_1") (pintype "passive"))
    )
    (net (code "63") (name "unconnected-(HT1-Pad4)") (class "Default")
      (node (ref "HT1") (pin "4") (pinfunction "4_4") (pintype "passive"))
    )
    (net (code "64") (name "unconnected-(HT1-Pad5)") (class "Default")
      (node (ref "HT1") (pin "5") (pinfunction "5_5") (pintype "passive"))
    )
    (net (code "65") (name "unconnected-(HT1-Pad6)") (class "Default")
      (node (ref "HT1") (pin "6") (pinfunction "6_6") (pintype "passive"))
    )
    (net (code "66") (name "unconnected-(HT2-Pad4)") (class "Default")
      (node (ref "HT2") (pin "4") (pinfunction "4_4") (pintype "passive"))
    )
    (net (code "67") (name "unconnected-(HT2-Pad5)") (class "Default")
      (node (ref "HT2") (pin "5") (pinfunction "5_5") (pintype "passive"))
    )
    (net (code "68") (name "unconnected-(HT2-Pad6)") (class "Default")
      (node (ref "HT2") (pin "6") (pinfunction "6_6") (pintype "passive"))
    )
    (net (code "69") (name "unconnected-(PT1-Pad4)") (class "Default")
      (node (ref "PT1") (pin "4") (pinfunction "4_4") (pintype "passive"))
    )
    (net (code "70") (name "unconnected-(PT1-Pad5)") (class "Default")
      (node (ref "PT1") (pin "5") (pinfunction "5_5") (pintype "passive"))
    )
    (net (code "71") (name "unconnected-(PT1-Pad6)") (class "Default")
      (node (ref "PT1") (pin "6") (pinfunction "6_6") (pintype "passive"))
    )
    (net (code "72") (name "unconnected-(VT1-Pad4)") (class "Default")
      (node (ref "VT1") (pin "4") (pinfunction "4_4") (pintype "passive"))
    )
    (net (code "73") (name "unconnected-(VT1-Pad5)") (class "Default")
      (node (ref "VT1") (pin "5") (pinfunction "5_5") (pintype "passive"))
    )
    (net (code "74") (name "unconnected-(VT1-Pad6)") (class "Default")
      (node (ref "VT1") (pin "6") (pinfunction "6_6") (pintype "passive"))
    )
  )
)
